# store-ctrl-block.net
KiCad netlist of a schematic drawn in EAGLE
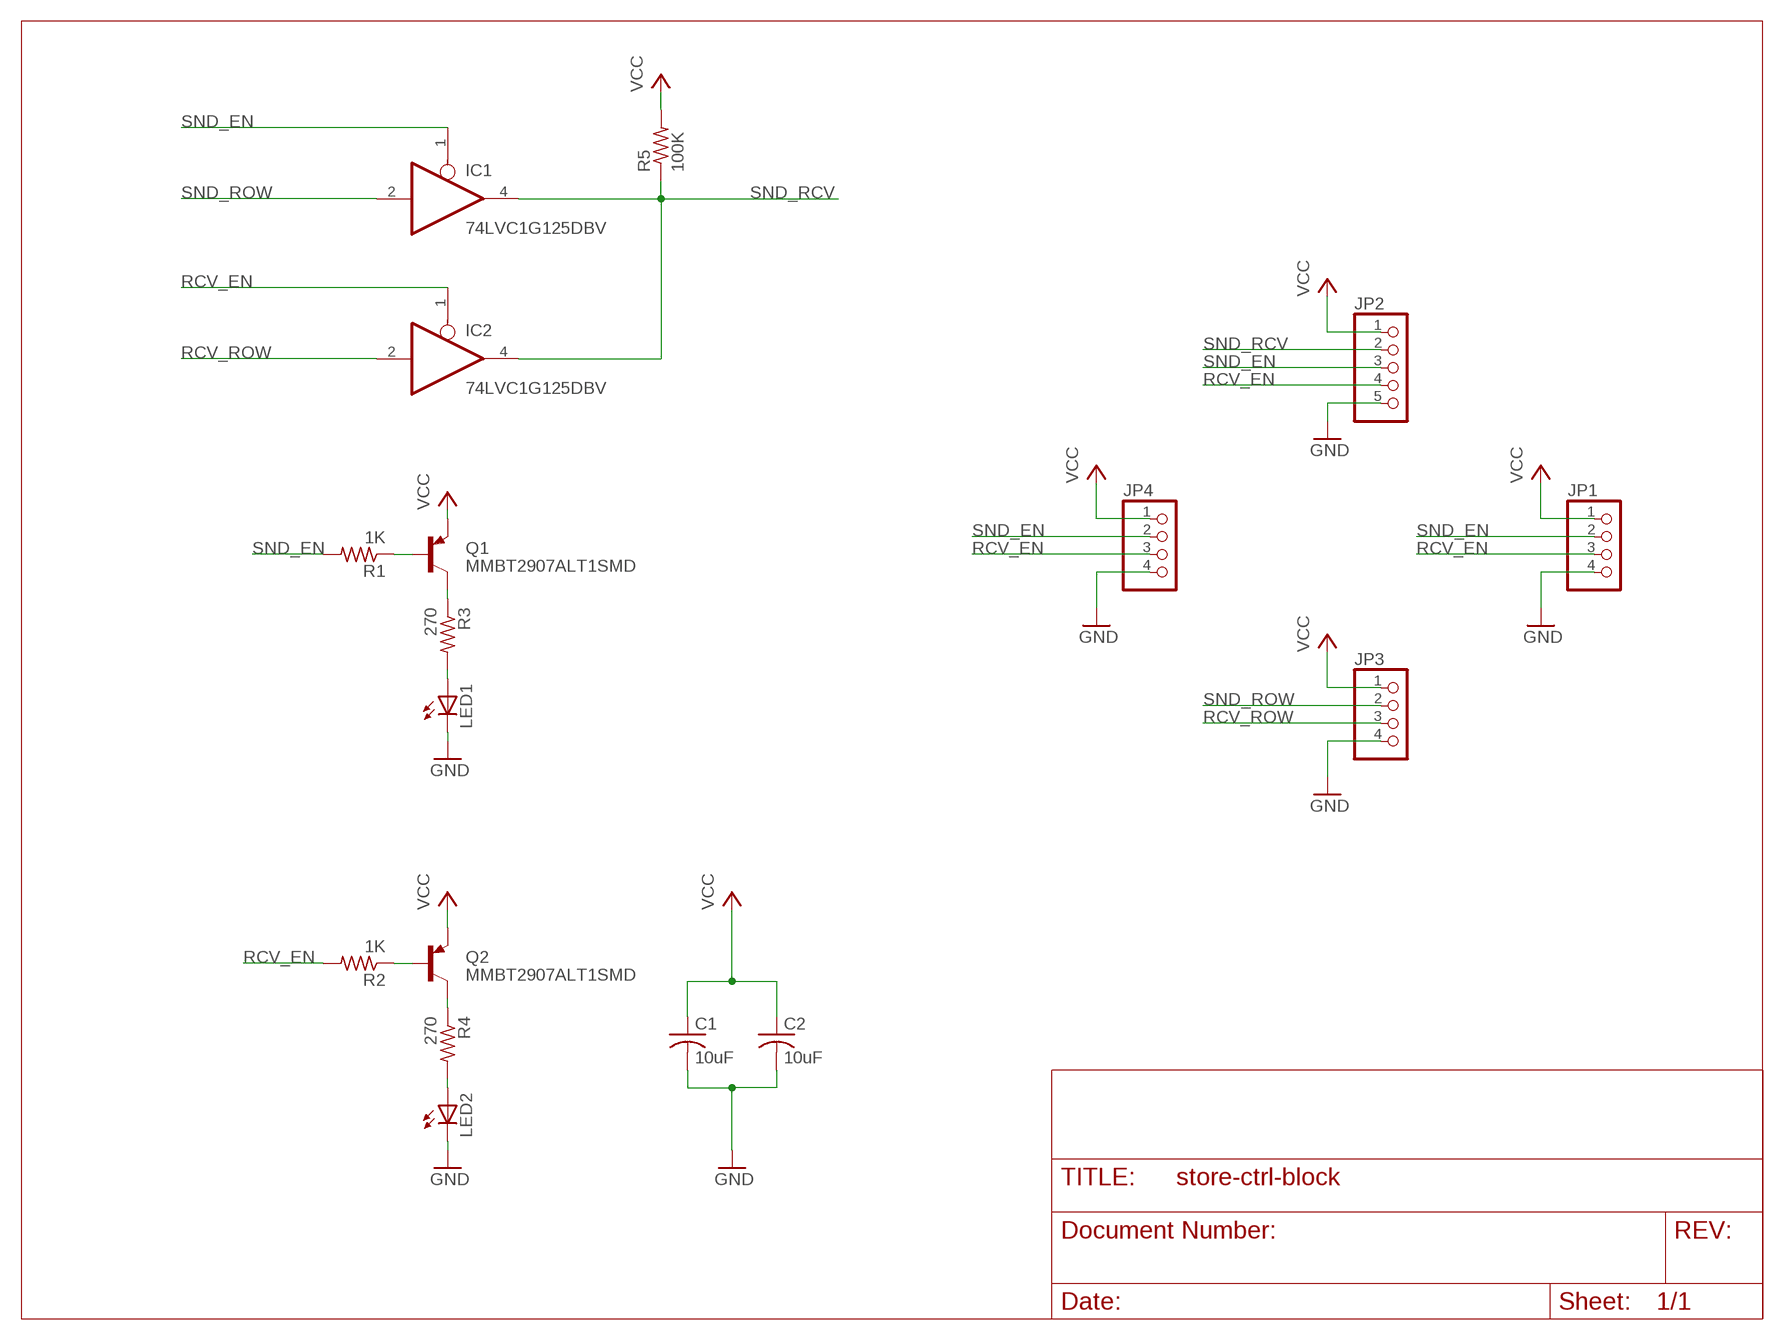
[diagram p0: schematic, sheet 1]

(export (version "E")
  (design (tool "Eeschema 10.0.6"))
  (components
    (comp (ref "C1")
      (value "10uF")
      (footprint "eagle-import:C0805")
      (libsource (lib "eagle-import") (part "C-USC0805"))
    )
    (comp (ref "C2")
      (value "10uF")
      (footprint "eagle-import:C0805")
      (libsource (lib "eagle-import") (part "C-USC0805"))
    )
    (comp (ref "IC1")
      (value "74LVC1G125DBV")
      (footprint "eagle-import:SOT23-5")
      (libsource (lib "eagle-import") (part "741G125DBVLVC"))
    )
    (comp (ref "IC2")
      (value "74LVC1G125DBV")
      (footprint "eagle-import:SOT23-5")
      (libsource (lib "eagle-import") (part "741G125DBVLVC"))
    )
    (comp (ref "JP1")
      (value "PINHD-1X4")
      (footprint "eagle-import:1X04")
      (libsource (lib "eagle-import") (part "PINHD-1X4"))
    )
    (comp (ref "JP2")
      (value "PINHD-1X5")
      (footprint "eagle-import:1X05")
      (libsource (lib "eagle-import") (part "PINHD-1X5"))
    )
    (comp (ref "JP3")
      (value "PINHD-1X4")
      (footprint "eagle-import:1X04")
      (libsource (lib "eagle-import") (part "PINHD-1X4"))
    )
    (comp (ref "JP4")
      (value "PINHD-1X4")
      (footprint "eagle-import:1X04")
      (libsource (lib "eagle-import") (part "PINHD-1X4"))
    )
    (comp (ref "LED1")
      (value "LEDCHIP-LED0805")
      (footprint "eagle-import:CHIP-LED0805")
      (libsource (lib "eagle-import") (part "LEDCHIP-LED0805"))
    )
    (comp (ref "LED2")
      (value "LEDCHIP-LED0805")
      (footprint "eagle-import:CHIP-LED0805")
      (libsource (lib "eagle-import") (part "LEDCHIP-LED0805"))
    )
    (comp (ref "Q1")
      (value "MMBT2907ALT1SMD")
      (footprint "eagle-import:SOT23-BEC")
      (libsource (lib "eagle-import") (part "MMBT2907SMDALT1"))
    )
    (comp (ref "Q2")
      (value "MMBT2907ALT1SMD")
      (footprint "eagle-import:SOT23-BEC")
      (libsource (lib "eagle-import") (part "MMBT2907SMDALT1"))
    )
    (comp (ref "R1")
      (value "1K")
      (footprint "eagle-import:R0805")
      (libsource (lib "eagle-import") (part "R-US_R0805"))
    )
    (comp (ref "R2")
      (value "1K")
      (footprint "eagle-import:R0805")
      (libsource (lib "eagle-import") (part "R-US_R0805"))
    )
    (comp (ref "R3")
      (value "270")
      (footprint "eagle-import:R0805")
      (libsource (lib "eagle-import") (part "R-US_R0805"))
    )
    (comp (ref "R4")
      (value "270")
      (footprint "eagle-import:R0805")
      (libsource (lib "eagle-import") (part "R-US_R0805"))
    )
    (comp (ref "R5")
      (value "100K")
      (footprint "eagle-import:R0805")
      (libsource (lib "eagle-import") (part "R-US_R0805"))
    )
  )
  (nets
    (net (code "1") (name "/RCV_EN") (class "Default")
      (node (ref "IC2") (pin "1") (pinfunction "OE_1") (pintype "input"))
      (node (ref "JP1") (pin "3") (pinfunction "3_3") (pintype "passive"))
      (node (ref "JP2") (pin "4") (pinfunction "4_4") (pintype "passive"))
      (node (ref "JP4") (pin "3") (pinfunction "3_3") (pintype "passive"))
      (node (ref "R2") (pin "2") (pinfunction "2_2") (pintype "passive"))
    )
    (net (code "2") (name "/RCV_ROW") (class "Default")
      (node (ref "IC2") (pin "2") (pinfunction "I_2") (pintype "input"))
      (node (ref "JP3") (pin "3") (pinfunction "3_3") (pintype "passive"))
    )
    (net (code "3") (name "/SND_EN") (class "Default")
      (node (ref "IC1") (pin "1") (pinfunction "OE_1") (pintype "input"))
      (node (ref "JP1") (pin "2") (pinfunction "2_2") (pintype "passive"))
      (node (ref "JP2") (pin "3") (pinfunction "3_3") (pintype "passive"))
      (node (ref "JP4") (pin "2") (pinfunction "2_2") (pintype "passive"))
      (node (ref "R1") (pin "2") (pinfunction "2_2") (pintype "passive"))
    )
    (net (code "4") (name "/SND_RCV") (class "Default")
      (node (ref "IC1") (pin "4") (pinfunction "O_4") (pintype "tri_state"))
      (node (ref "IC2") (pin "4") (pinfunction "O_4") (pintype "tri_state"))
      (node (ref "JP2") (pin "2") (pinfunction "2_2") (pintype "passive"))
      (node (ref "R5") (pin "1") (pinfunction "1_1") (pintype "passive"))
    )
    (net (code "5") (name "/SND_ROW") (class "Default")
      (node (ref "IC1") (pin "2") (pinfunction "I_2") (pintype "input"))
      (node (ref "JP3") (pin "2") (pinfunction "2_2") (pintype "passive"))
    )
    (net (code "6") (name "GND") (class "Default")
      (node (ref "C1") (pin "2") (pinfunction "2_2") (pintype "passive"))
      (node (ref "C2") (pin "2") (pinfunction "2_2") (pintype "passive"))
      (node (ref "JP1") (pin "4") (pinfunction "4_4") (pintype "passive"))
      (node (ref "JP2") (pin "5") (pinfunction "5_5") (pintype "passive"))
      (node (ref "JP3") (pin "4") (pinfunction "4_4") (pintype "passive"))
      (node (ref "JP4") (pin "4") (pinfunction "4_4") (pintype "passive"))
      (node (ref "LED1") (pin "C") (pinfunction "C_C") (pintype "passive"))
      (node (ref "LED2") (pin "C") (pinfunction "C_C") (pintype "passive"))
    )
    (net (code "7") (name "Net-(LED1-PadA)") (class "Default")
      (node (ref "LED1") (pin "A") (pinfunction "A_A") (pintype "passive"))
      (node (ref "R3") (pin "2") (pinfunction "2_2") (pintype "passive"))
    )
    (net (code "8") (name "Net-(LED2-PadA)") (class "Default")
      (node (ref "LED2") (pin "A") (pinfunction "A_A") (pintype "passive"))
      (node (ref "R4") (pin "2") (pinfunction "2_2") (pintype "passive"))
    )
    (net (code "9") (name "Net-(Q1-PadB)") (class "Default")
      (node (ref "Q1") (pin "B") (pinfunction "B_B") (pintype "passive"))
      (node (ref "R1") (pin "1") (pinfunction "1_1") (pintype "passive"))
    )
    (net (code "10") (name "Net-(Q1-PadC)") (class "Default")
      (node (ref "Q1") (pin "C") (pinfunction "C_C") (pintype "passive"))
      (node (ref "R3") (pin "1") (pinfunction "1_1") (pintype "passive"))
    )
    (net (code "11") (name "Net-(Q2-PadB)") (class "Default")
      (node (ref "Q2") (pin "B") (pinfunction "B_B") (pintype "passive"))
      (node (ref "R2") (pin "1") (pinfunction "1_1") (pintype "passive"))
    )
    (net (code "12") (name "Net-(Q2-PadC)") (class "Default")
      (node (ref "Q2") (pin "C") (pinfunction "C_C") (pintype "passive"))
      (node (ref "R4") (pin "1") (pinfunction "1_1") (pintype "passive"))
    )
    (net (code "13") (name "VCC") (class "Default")
      (node (ref "C1") (pin "1") (pinfunction "1_1") (pintype "passive"))
      (node (ref "C2") (pin "1") (pinfunction "1_1") (pintype "passive"))
      (node (ref "JP1") (pin "1") (pinfunction "1_1") (pintype "passive"))
      (node (ref "JP2") (pin "1") (pinfunction "1_1") (pintype "passive"))
      (node (ref "JP3") (pin "1") (pinfunction "1_1") (pintype "passive"))
      (node (ref "JP4") (pin "1") (pinfunction "1_1") (pintype "passive"))
      (node (ref "Q1") (pin "E") (pinfunction "E_E") (pintype "passive"))
      (node (ref "Q2") (pin "E") (pinfunction "E_E") (pintype "passive"))
      (node (ref "R5") (pin "2") (pinfunction "2_2") (pintype "passive"))
    )
  )
)
